# ProPrj_alba_2026-09-08.net
KiCad netlist of a schematic drawn in EasyEDA Pro
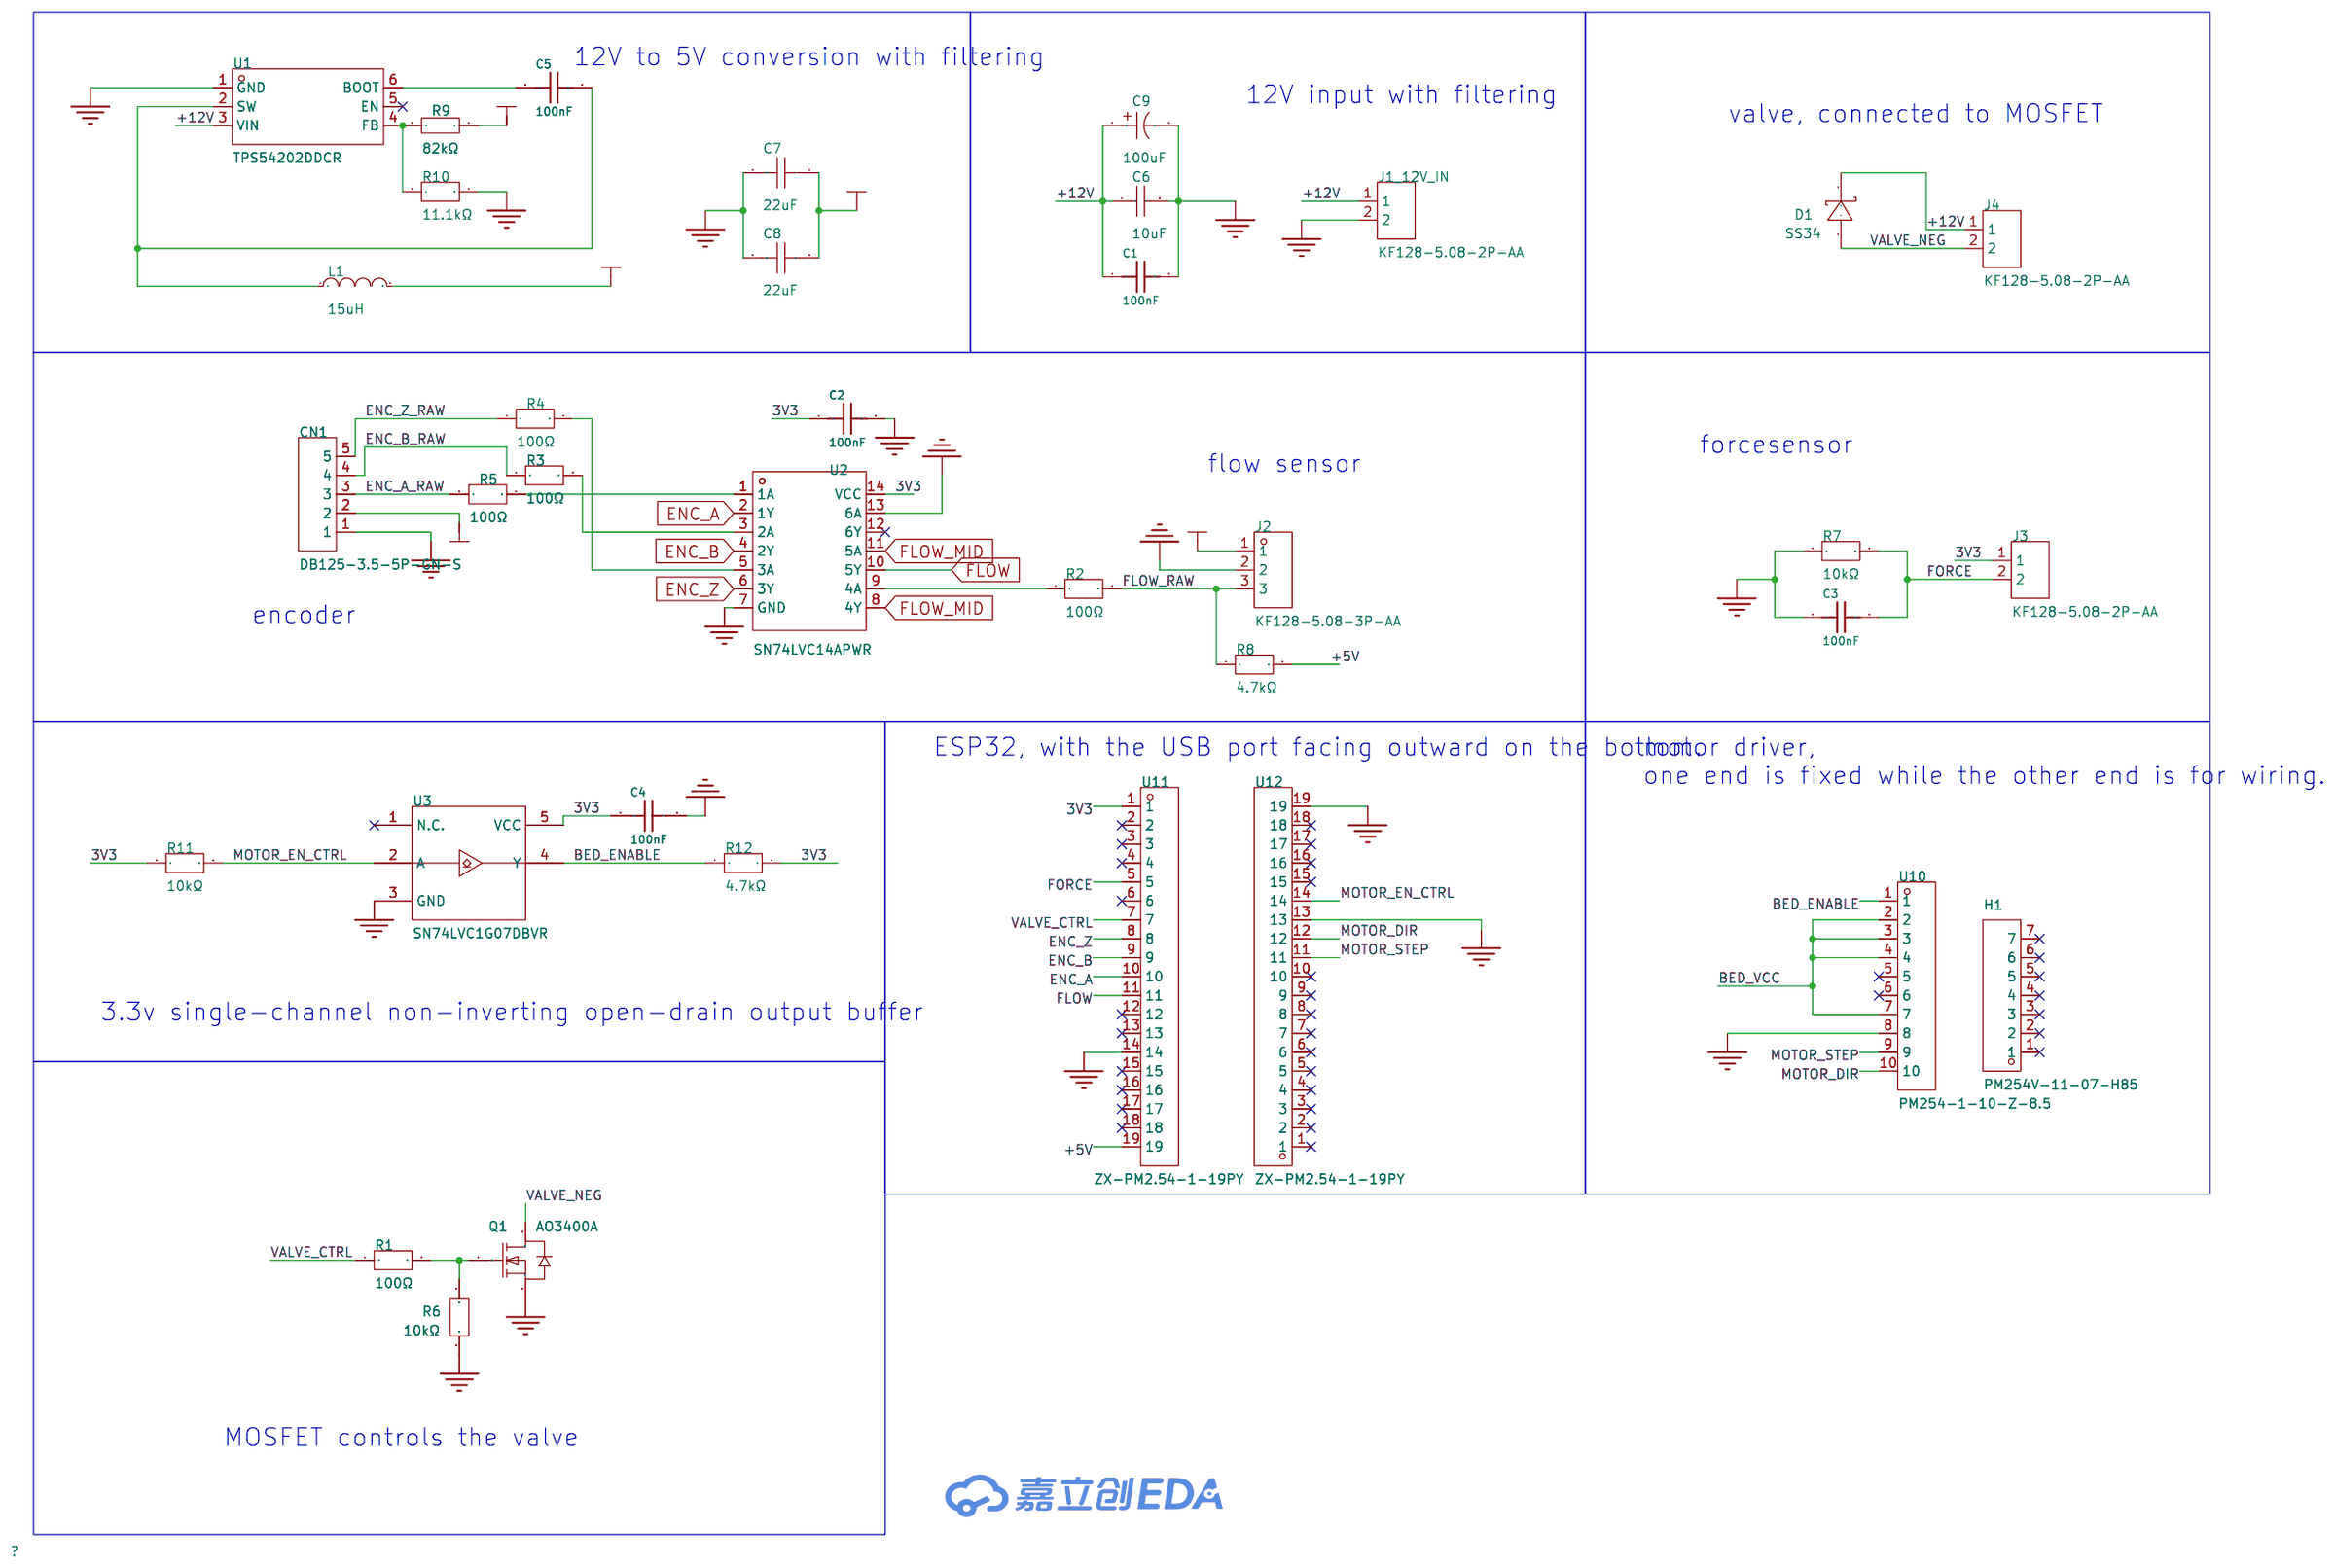
[diagram p0: schematic sheet]

(export (version "E")
  (design (tool "Eeschema 10.0.6"))
  (components
    (comp (ref "C1")
      (value "100nF")
      (footprint "easyedapro:C0603")
      (description "容值:100nF;精度:±10%;额定电压:50V;温度系数:X7R;")
      (fields
        (field (name "Manufacturer Part") "CC0603KRX7R9BB104")
        (field (name "Manufacturer") "YAGEO(国巨)")
      )
      (libsource (lib "easyedapro") (part "CC0603KRX7R9BB104"))
    )
    (comp (ref "C2")
      (value "100nF")
      (footprint "easyedapro:C0603")
      (description "容值:100nF;精度:±10%;额定电压:50V;温度系数:X7R;")
      (fields
        (field (name "Manufacturer Part") "CC0603KRX7R9BB104")
        (field (name "Manufacturer") "YAGEO(国巨)")
      )
      (libsource (lib "easyedapro") (part "CC0603KRX7R9BB104"))
    )
    (comp (ref "C3")
      (value "100nF")
      (footprint "easyedapro:C0603")
      (description "容值:100nF;精度:±10%;额定电压:50V;温度系数:X7R;")
      (fields
        (field (name "Manufacturer Part") "CC0603KRX7R9BB104")
        (field (name "Manufacturer") "YAGEO(国巨)")
      )
      (libsource (lib "easyedapro") (part "CC0603KRX7R9BB104"))
    )
    (comp (ref "C4")
      (value "100nF")
      (footprint "easyedapro:C0603")
      (description "容值:100nF;精度:±10%;额定电压:50V;温度系数:X7R;")
      (fields
        (field (name "Manufacturer Part") "CC0603KRX7R9BB104")
        (field (name "Manufacturer") "YAGEO(国巨)")
      )
      (libsource (lib "easyedapro") (part "CC0603KRX7R9BB104"))
    )
    (comp (ref "C5")
      (value "100nF")
      (footprint "easyedapro:C0603")
      (description "容值:100nF;精度:±10%;额定电压:50V;温度系数:X7R;")
      (fields
        (field (name "Manufacturer Part") "CC0603KRX7R9BB104")
        (field (name "Manufacturer") "YAGEO(国巨)")
      )
      (libsource (lib "easyedapro") (part "CC0603KRX7R9BB104"))
    )
    (comp (ref "C6")
      (value "10uF")
      (footprint "easyedapro:C1206")
      (description "容值:10uF;精度:±10%;额定电压:50V;温度系数:X5R;")
      (fields
        (field (name "Manufacturer Part") "CL31A106KBHNNNE")
        (field (name "Manufacturer") "SAMSUNG(三星)")
      )
      (libsource (lib "easyedapro") (part "CL31A106KBHNNNE"))
    )
    (comp (ref "C7")
      (value "22uF")
      (footprint "easyedapro:C1206")
      (description "容值:22uF;精度:±20%;额定电压:10V;温度系数:X5R;")
      (fields (field (name "Manufacturer Part") "1206X226M100NT") (field (name "Manufacturer") "FH(风华)"))
      (libsource (lib "easyedapro") (part "1206X226M100NT"))
    )
    (comp (ref "C8")
      (value "22uF")
      (footprint "easyedapro:C1206")
      (description "容值:22uF;精度:±20%;额定电压:10V;温度系数:X5R;")
      (fields (field (name "Manufacturer Part") "1206X226M100NT") (field (name "Manufacturer") "FH(风华)"))
      (libsource (lib "easyedapro") (part "1206X226M100NT"))
    )
    (comp (ref "C9")
      (value "100uF")
      (footprint "easyedapro:CAP-SMD_BD6.3-L6.6-W6.6-LS7.2-FD-1")
      (description "容值:100uF;精度:±20%;额定电压:25V;纹波电流:93mA@120Hz;等效串联电阻(ESR):-;")
      (fields
        (field (name "Manufacturer Part") "RVT1E101M0607 100UF 25V")
        (field (name "Manufacturer") "DMBJ(振宝佳)")
      )
      (libsource (lib "easyedapro") (part "RVT1E101M0607 100UF 25V"))
    )
    (comp (ref "CN1")
      (value "DB125-3.5-5P-GN-S")
      (footprint "easyedapro:CONN-TH_5P-P3.50_DORABO_DB125-3.5-5P-GN-S")
      (fields (field (name "Manufacturer") "DORABO(地博电气)"))
      (libsource (lib "easyedapro") (part "DB125-3.5-5P-GN-S"))
    )
    (comp (ref "D1")
      (value "SS34")
      (footprint "easyedapro:SMA_L4.3-W2.6-LS5.2-RD")
      (description "二极管配置:独立式;正向压降(Vf):550mV@3A;直流反向耐压(Vr):40V;整流电流:3A;")
      (fields (field (name "Manufacturer") "MDD(辰达半导体)"))
      (libsource (lib "easyedapro") (part "SS34_C8678"))
    )
    (comp (ref "H1")
      (value "PM254V-11-07-H85")
      (footprint "easyedapro:HDR-TH_7P-P2.54-V-F")
      (fields (field (name "Manufacturer") "XFCN(兴飞)"))
      (libsource (lib "easyedapro") (part "PM254V-11-07-H85"))
    )
    (comp (ref "J1_12V_IN")
      (value "KF128-5.08-2P-AA")
      (footprint "easyedapro:CONN-TH_P5.08_KF128-5.08-2P")
      (fields (field (name "Manufacturer") "KEFA(科发)"))
      (libsource (lib "easyedapro") (part "KF128-5.08-2P"))
    )
    (comp (ref "J2")
      (value "KF128-5.08-3P-AA")
      (footprint "easyedapro:CONN-TH_3P-P5.08_KF128-5.08-3P")
      (fields (field (name "Manufacturer") "KEFA(科发)"))
      (libsource (lib "easyedapro") (part "KF128-5.08-3P"))
    )
    (comp (ref "J3")
      (value "KF128-5.08-2P-AA")
      (footprint "easyedapro:CONN-TH_P5.08_KF128-5.08-2P")
      (fields (field (name "Manufacturer") "KEFA(科发)"))
      (libsource (lib "easyedapro") (part "KF128-5.08-2P"))
    )
    (comp (ref "J4")
      (value "KF128-5.08-2P-AA")
      (footprint "easyedapro:CONN-TH_P5.08_KF128-5.08-2P")
      (fields (field (name "Manufacturer") "KEFA(科发)"))
      (libsource (lib "easyedapro") (part "KF128-5.08-2P"))
    )
    (comp (ref "L1")
      (value "15uH")
      (footprint "easyedapro:IND-SMD_L7.2-W6.6_GPSR07X0")
      (description "电感值:15uH;精度:±20%;额定电流:3A;直流电阻(DCR):98mΩ;")
      (fields (field (name "Manufacturer Part") "CYA0630-15UH") (field (name "Manufacturer") "SHOU HAN(首韩)"))
      (libsource (lib "easyedapro") (part "CYA0630-15UH"))
    )
    (comp (ref "Q1")
      (value "AO3400A")
      (footprint "easyedapro:SOT-23-3_L2.9-W1.3-P1.90-LS2.4-BR")
      (description "数量:-;漏源电压(Vdss):30V;连续漏极电流(Id):-;导通电阻(RDS(on)):48mΩ@2.5V;耗散功率(Pd):-;阈值电压(Vgs(th)):1.45V@250uA;")
      (fields (field (name "Manufacturer") "AOS"))
      (libsource (lib "easyedapro") (part "AO3400A"))
    )
    (comp (ref "R1")
      (value "100Ω")
      (footprint "easyedapro:R0603")
      (description "电阻类型:厚膜电阻;阻值:100Ω;精度:±1%;功率:100mW;工作电压:75V;温度系数:±100ppm/°C;")
      (fields (field (name "Manufacturer Part") "FRC0603F1000TS") (field (name "Manufacturer") "FOJAN(富捷)"))
      (libsource (lib "easyedapro") (part "FRC0603F1000TS"))
    )
    (comp (ref "R2")
      (value "100Ω")
      (footprint "easyedapro:R0603")
      (description "电阻类型:厚膜电阻;阻值:100Ω;精度:±1%;功率:100mW;工作电压:75V;温度系数:±100ppm/°C;")
      (fields (field (name "Manufacturer Part") "FRC0603F1000TS") (field (name "Manufacturer") "FOJAN(富捷)"))
      (libsource (lib "easyedapro") (part "FRC0603F1000TS"))
    )
    (comp (ref "R3")
      (value "100Ω")
      (footprint "easyedapro:R0603")
      (description "电阻类型:厚膜电阻;阻值:100Ω;精度:±1%;功率:100mW;工作电压:75V;温度系数:±100ppm/°C;")
      (fields (field (name "Manufacturer Part") "FRC0603F1000TS") (field (name "Manufacturer") "FOJAN(富捷)"))
      (libsource (lib "easyedapro") (part "FRC0603F1000TS"))
    )
    (comp (ref "R4")
      (value "100Ω")
      (footprint "easyedapro:R0603")
      (description "电阻类型:厚膜电阻;阻值:100Ω;精度:±1%;功率:100mW;工作电压:75V;温度系数:±100ppm/°C;")
      (fields (field (name "Manufacturer Part") "FRC0603F1000TS") (field (name "Manufacturer") "FOJAN(富捷)"))
      (libsource (lib "easyedapro") (part "FRC0603F1000TS"))
    )
    (comp (ref "R5")
      (value "100Ω")
      (footprint "easyedapro:R0603")
      (description "电阻类型:厚膜电阻;阻值:100Ω;精度:±1%;功率:100mW;工作电压:75V;温度系数:±100ppm/°C;")
      (fields (field (name "Manufacturer Part") "FRC0603F1000TS") (field (name "Manufacturer") "FOJAN(富捷)"))
      (libsource (lib "easyedapro") (part "FRC0603F1000TS"))
    )
    (comp (ref "R6")
      (value "10kΩ")
      (footprint "easyedapro:R0603")
      (description "电阻类型:厚膜电阻;阻值:10kΩ;精度:±1%;功率:100mW;工作电压:75V;温度系数:±100ppm/°C;")
      (fields (field (name "Manufacturer Part") "FRC0603F1002TS") (field (name "Manufacturer") "FOJAN(富捷)"))
      (libsource (lib "easyedapro") (part "FRC0603F1002TS"))
    )
    (comp (ref "R7")
      (value "10kΩ")
      (footprint "easyedapro:R0603")
      (description "电阻类型:厚膜电阻;阻值:10kΩ;精度:±1%;功率:100mW;工作电压:75V;温度系数:±100ppm/°C;")
      (fields (field (name "Manufacturer Part") "FRC0603F1002TS") (field (name "Manufacturer") "FOJAN(富捷)"))
      (libsource (lib "easyedapro") (part "FRC0603F1002TS"))
    )
    (comp (ref "R8")
      (value "4.7kΩ")
      (footprint "easyedapro:R0603")
      (description "电阻类型:厚膜电阻;阻值:4.7kΩ;精度:±1%;功率:100mW;工作电压:75V;温度系数:±100ppm/°C;")
      (fields (field (name "Manufacturer Part") "FRC0603F4701TS") (field (name "Manufacturer") "FOJAN(富捷)"))
      (libsource (lib "easyedapro") (part "FRC0603F4701TS"))
    )
    (comp (ref "R9")
      (value "82kΩ")
      (footprint "easyedapro:R0603")
      (description "电阻类型:厚膜电阻;阻值:82kΩ;精度:±1%;功率:100mW;工作电压:75V;温度系数:±100ppm/°C;")
      (fields
        (field (name "Manufacturer Part") "0603WAF8202T5E")
        (field (name "Manufacturer") "UNI-ROYAL(厚声)")
      )
      (libsource (lib "easyedapro") (part "0603WAF8202T5E"))
    )
    (comp (ref "R10")
      (value "11.1kΩ")
      (footprint "easyedapro:R0603")
      (description "电阻类型:薄膜电阻;阻值:11.1kΩ;精度:±0.1%;功率:125mW;工作电压:75V;温度系数:±25ppm/°C;")
      (fields
        (field (name "Manufacturer Part") "TNPW060311K1BEEA")
        (field (name "Manufacturer") "VISHAY(威世)")
      )
      (libsource (lib "easyedapro") (part "TNPW060311K1BEEA"))
    )
    (comp (ref "R11")
      (value "10kΩ")
      (footprint "easyedapro:R0603")
      (description "电阻类型:厚膜电阻;阻值:10kΩ;精度:±1%;功率:100mW;工作电压:75V;温度系数:±100ppm/°C;")
      (fields (field (name "Manufacturer Part") "FRC0603F1002TS") (field (name "Manufacturer") "FOJAN(富捷)"))
      (libsource (lib "easyedapro") (part "FRC0603F1002TS"))
    )
    (comp (ref "R12")
      (value "4.7kΩ")
      (footprint "easyedapro:R0603")
      (description "电阻类型:厚膜电阻;阻值:4.7kΩ;精度:±1%;功率:100mW;工作电压:75V;温度系数:±100ppm/°C;")
      (fields (field (name "Manufacturer Part") "FRC0603F4701TS") (field (name "Manufacturer") "FOJAN(富捷)"))
      (libsource (lib "easyedapro") (part "FRC0603F4701TS"))
    )
    (comp (ref "U1")
      (value "TPS54202DDCR")
      (footprint "easyedapro:SOT-23-6_L2.9-W1.6-P0.95-LS2.8-BL")
      (description "功能类型:降压型;工作电压:4.5V~28V;输出电压:-;输出电流:2A;输出类型:可调;")
      (fields (field (name "Manufacturer") "TI(德州仪器)"))
      (libsource (lib "easyedapro") (part "TPS54202DDCR"))
    )
    (comp (ref "U2")
      (value "SN74LVC14APWR")
      (footprint "easyedapro:TSSOP-14_L5.0-W4.4-P0.65-LS6.4-BL")
      (description "输入类型:施密特触发器;工作电压:1.65V~3.6V;静态电流(Iq):1uA;通道数:6;传播延迟(tpd):6.2ns@3.3V,50pF;")
      (fields (field (name "Manufacturer") "TI(德州仪器)"))
      (libsource (lib "easyedapro") (part "SN74LVC14APWRG4"))
    )
    (comp (ref "U3")
      (value "SN74LVC1G07DBVR")
      (footprint "easyedapro:SOT-23-5_L3.0-W1.7-P0.95-LS2.8-BR")
      (description "输入类型:-;工作电压:1.65V~5.5V;元件数:1;每个元件位数:1;灌电流(IOL):32mA;拉电流(IOH):-;")
      (fields (field (name "Manufacturer") "TI(德州仪器)"))
      (libsource (lib "easyedapro") (part "SN74LVC1G07DBVR"))
    )
    (comp (ref "U10")
      (value "PM254-1-10-Z-8.5")
      (footprint "easyedapro:HDR-TH_10P-P2.54-V-F")
      (fields (field (name "Manufacturer") "HCTL(华灿天禄)"))
      (libsource (lib "easyedapro") (part "PM254-1-10-Z-8.5"))
    )
    (comp (ref "U11")
      (value "ZX-PM2.54-1-19PY")
      (footprint "easyedapro:HDR-TH_19P-P2.54-V-F")
      (fields (field (name "Manufacturer") "Megastar(兆星)"))
      (libsource (lib "easyedapro") (part "ZX-PM2.54-1-19PY"))
    )
    (comp (ref "U12")
      (value "ZX-PM2.54-1-19PY")
      (footprint "easyedapro:HDR-TH_19P-P2.54-V-F")
      (fields (field (name "Manufacturer") "Megastar(兆星)"))
      (libsource (lib "easyedapro") (part "ZX-PM2.54-1-19PY"))
    )
  )
  (nets
    (net (code "1") (name "+5V") (class "Default")
      (node (ref "C7") (pin "1") (pinfunction "1_1") (pintype "unspecified"))
      (node (ref "C8") (pin "1") (pinfunction "1_1") (pintype "unspecified"))
      (node (ref "CN1") (pin "2") (pinfunction "2_2") (pintype "unspecified"))
      (node (ref "J2") (pin "1") (pinfunction "1_1") (pintype "unspecified"))
      (node (ref "L1") (pin "2") (pinfunction "2_2") (pintype "unspecified"))
      (node (ref "R8") (pin "2") (pinfunction "2_2") (pintype "unspecified"))
      (node (ref "R9") (pin "2") (pinfunction "2_2") (pintype "input"))
      (node (ref "U11") (pin "19") (pinfunction "19_19") (pintype "unspecified"))
    )
    (net (code "2") (name "/+12V") (class "Default")
      (node (ref "C1") (pin "1") (pinfunction "1_1") (pintype "unspecified"))
      (node (ref "C6") (pin "1") (pinfunction "1_1") (pintype "input"))
      (node (ref "C9") (pin "1") (pinfunction "1_1") (pintype "input"))
      (node (ref "D1") (pin "1") (pinfunction "K_1") (pintype "unspecified"))
      (node (ref "J1_12V_IN") (pin "1") (pinfunction "1_1") (pintype "unspecified"))
      (node (ref "J4") (pin "1") (pinfunction "1_1") (pintype "unspecified"))
      (node (ref "U1") (pin "3") (pinfunction "VIN_3") (pintype "unspecified"))
    )
    (net (code "3") (name "/3V3") (class "Default")
      (node (ref "C2") (pin "1") (pinfunction "1_1") (pintype "unspecified"))
      (node (ref "C4") (pin "1") (pinfunction "1_1") (pintype "unspecified"))
      (node (ref "J3") (pin "1") (pinfunction "1_1") (pintype "unspecified"))
      (node (ref "R11") (pin "1") (pinfunction "1_1") (pintype "unspecified"))
      (node (ref "R12") (pin "2") (pinfunction "2_2") (pintype "unspecified"))
      (node (ref "U11") (pin "1") (pinfunction "1_1") (pintype "unspecified"))
      (node (ref "U2") (pin "14") (pinfunction "VCC_14") (pintype "unspecified"))
      (node (ref "U3") (pin "5") (pinfunction "VCC_5") (pintype "unspecified"))
    )
    (net (code "4") (name "/BED_ENABLE") (class "Default")
      (node (ref "R12") (pin "1") (pinfunction "1_1") (pintype "unspecified"))
      (node (ref "U10") (pin "1") (pinfunction "1_1") (pintype "unspecified"))
      (node (ref "U3") (pin "4") (pinfunction "Y_4") (pintype "unspecified"))
    )
    (net (code "5") (name "/BED_VCC") (class "Default")
      (node (ref "U10") (pin "2") (pinfunction "2_2") (pintype "unspecified"))
      (node (ref "U10") (pin "3") (pinfunction "3_3") (pintype "unspecified"))
      (node (ref "U10") (pin "4") (pinfunction "4_4") (pintype "unspecified"))
      (node (ref "U10") (pin "7") (pinfunction "7_7") (pintype "unspecified"))
    )
    (net (code "6") (name "/ENC_A_RAW") (class "Default")
      (node (ref "CN1") (pin "3") (pinfunction "3_3") (pintype "unspecified"))
      (node (ref "R5") (pin "1") (pinfunction "1_1") (pintype "unspecified"))
    )
    (net (code "7") (name "/ENC_B_RAW") (class "Default")
      (node (ref "CN1") (pin "4") (pinfunction "4_4") (pintype "unspecified"))
      (node (ref "R3") (pin "1") (pinfunction "1_1") (pintype "unspecified"))
    )
    (net (code "8") (name "/ENC_Z_RAW") (class "Default")
      (node (ref "CN1") (pin "5") (pinfunction "5_5") (pintype "unspecified"))
      (node (ref "R4") (pin "1") (pinfunction "1_1") (pintype "unspecified"))
    )
    (net (code "9") (name "/FLOW_RAW") (class "Default")
      (node (ref "J2") (pin "3") (pinfunction "3_3") (pintype "unspecified"))
      (node (ref "R2") (pin "2") (pinfunction "2_2") (pintype "unspecified"))
      (node (ref "R8") (pin "1") (pinfunction "1_1") (pintype "unspecified"))
    )
    (net (code "10") (name "/FORCE") (class "Default")
      (node (ref "C3") (pin "2") (pinfunction "2_2") (pintype "unspecified"))
      (node (ref "J3") (pin "2") (pinfunction "2_2") (pintype "unspecified"))
      (node (ref "R7") (pin "2") (pinfunction "2_2") (pintype "unspecified"))
      (node (ref "U11") (pin "5") (pinfunction "5_5") (pintype "unspecified"))
    )
    (net (code "11") (name "/MOTOR_DIR") (class "Default")
      (node (ref "U10") (pin "10") (pinfunction "10_10") (pintype "unspecified"))
      (node (ref "U12") (pin "12") (pinfunction "12_12") (pintype "unspecified"))
    )
    (net (code "12") (name "/MOTOR_EN_CTRL") (class "Default")
      (node (ref "R11") (pin "2") (pinfunction "2_2") (pintype "unspecified"))
      (node (ref "U12") (pin "14") (pinfunction "14_14") (pintype "unspecified"))
      (node (ref "U3") (pin "2") (pinfunction "A_2") (pintype "unspecified"))
    )
    (net (code "13") (name "/MOTOR_STEP") (class "Default")
      (node (ref "U10") (pin "9") (pinfunction "9_9") (pintype "unspecified"))
      (node (ref "U12") (pin "11") (pinfunction "11_11") (pintype "unspecified"))
    )
    (net (code "14") (name "/VALVE_CTRL") (class "Default")
      (node (ref "R1") (pin "1") (pinfunction "1_1") (pintype "unspecified"))
      (node (ref "U11") (pin "7") (pinfunction "7_7") (pintype "unspecified"))
    )
    (net (code "15") (name "/VALVE_NEG") (class "Default")
      (node (ref "D1") (pin "2") (pinfunction "A_2") (pintype "unspecified"))
      (node (ref "J4") (pin "2") (pinfunction "2_2") (pintype "unspecified"))
      (node (ref "Q1") (pin "3") (pinfunction "D_3") (pintype "unspecified"))
    )
    (net (code "16") (name "ENC_A") (class "Default")
      (node (ref "U11") (pin "10") (pinfunction "10_10") (pintype "unspecified"))
      (node (ref "U2") (pin "2") (pinfunction "1Y_2") (pintype "unspecified"))
    )
    (net (code "17") (name "ENC_B") (class "Default")
      (node (ref "U11") (pin "9") (pinfunction "9_9") (pintype "unspecified"))
      (node (ref "U2") (pin "4") (pinfunction "2Y_4") (pintype "unspecified"))
    )
    (net (code "18") (name "ENC_Z") (class "Default")
      (node (ref "U11") (pin "8") (pinfunction "8_8") (pintype "unspecified"))
      (node (ref "U2") (pin "6") (pinfunction "3Y_6") (pintype "unspecified"))
    )
    (net (code "19") (name "FLOW") (class "Default")
      (node (ref "U11") (pin "11") (pinfunction "11_11") (pintype "unspecified"))
      (node (ref "U2") (pin "10") (pinfunction "5Y_10") (pintype "unspecified"))
    )
    (net (code "20") (name "FLOW_MID") (class "Default")
      (node (ref "U2") (pin "11") (pinfunction "5A_11") (pintype "unspecified"))
      (node (ref "U2") (pin "8") (pinfunction "4Y_8") (pintype "unspecified"))
    )
    (net (code "21") (name "GND") (class "Default")
      (node (ref "C1") (pin "2") (pinfunction "2_2") (pintype "unspecified"))
      (node (ref "C2") (pin "2") (pinfunction "2_2") (pintype "unspecified"))
      (node (ref "C3") (pin "1") (pinfunction "1_1") (pintype "unspecified"))
      (node (ref "C4") (pin "2") (pinfunction "2_2") (pintype "unspecified"))
      (node (ref "C6") (pin "2") (pinfunction "2_2") (pintype "input"))
      (node (ref "C7") (pin "2") (pinfunction "2_2") (pintype "unspecified"))
      (node (ref "C8") (pin "2") (pinfunction "2_2") (pintype "unspecified"))
      (node (ref "C9") (pin "2") (pinfunction "2_2") (pintype "input"))
      (node (ref "CN1") (pin "1") (pinfunction "1_1") (pintype "unspecified"))
      (node (ref "J1_12V_IN") (pin "2") (pinfunction "2_2") (pintype "unspecified"))
      (node (ref "J2") (pin "2") (pinfunction "2_2") (pintype "unspecified"))
      (node (ref "Q1") (pin "2") (pinfunction "S_2") (pintype "unspecified"))
      (node (ref "R10") (pin "2") (pinfunction "2_2") (pintype "unspecified"))
      (node (ref "R6") (pin "1") (pinfunction "1_1") (pintype "unspecified"))
      (node (ref "R7") (pin "1") (pinfunction "1_1") (pintype "unspecified"))
      (node (ref "U1") (pin "1") (pinfunction "GND_1") (pintype "unspecified"))
      (node (ref "U10") (pin "8") (pinfunction "8_8") (pintype "unspecified"))
      (node (ref "U11") (pin "14") (pinfunction "14_14") (pintype "unspecified"))
      (node (ref "U12") (pin "13") (pinfunction "13_13") (pintype "unspecified"))
      (node (ref "U12") (pin "19") (pinfunction "19_19") (pintype "unspecified"))
      (node (ref "U2") (pin "13") (pinfunction "6A_13") (pintype "unspecified"))
      (node (ref "U2") (pin "7") (pinfunction "GND_7") (pintype "unspecified"))
      (node (ref "U3") (pin "3") (pinfunction "GND_3") (pintype "unspecified"))
    )
    (net (code "22") (name "Net-(Q1-G)") (class "Default")
      (node (ref "Q1") (pin "1") (pinfunction "G_1") (pintype "unspecified"))
      (node (ref "R1") (pin "2") (pinfunction "2_2") (pintype "unspecified"))
      (node (ref "R6") (pin "2") (pinfunction "2_2") (pintype "unspecified"))
    )
    (net (code "23") (name "Net-(U1-BOOT)") (class "Default")
      (node (ref "C5") (pin "1") (pinfunction "1_1") (pintype "unspecified"))
      (node (ref "U1") (pin "6") (pinfunction "BOOT_6") (pintype "unspecified"))
    )
    (net (code "24") (name "Net-(U1-FB)") (class "Default")
      (node (ref "R10") (pin "1") (pinfunction "1_1") (pintype "unspecified"))
      (node (ref "R9") (pin "1") (pinfunction "1_1") (pintype "input"))
      (node (ref "U1") (pin "4") (pinfunction "FB_4") (pintype "unspecified"))
    )
    (net (code "25") (name "Net-(U1-SW)") (class "Default")
      (node (ref "C5") (pin "2") (pinfunction "2_2") (pintype "unspecified"))
      (node (ref "L1") (pin "1") (pinfunction "1_1") (pintype "unspecified"))
      (node (ref "U1") (pin "2") (pinfunction "SW_2") (pintype "unspecified"))
    )
    (net (code "26") (name "Net-(U2-1A)") (class "Default")
      (node (ref "R5") (pin "2") (pinfunction "2_2") (pintype "unspecified"))
      (node (ref "U2") (pin "1") (pinfunction "1A_1") (pintype "unspecified"))
    )
    (net (code "27") (name "Net-(U2-2A)") (class "Default")
      (node (ref "R3") (pin "2") (pinfunction "2_2") (pintype "unspecified"))
      (node (ref "U2") (pin "3") (pinfunction "2A_3") (pintype "unspecified"))
    )
    (net (code "28") (name "Net-(U2-3A)") (class "Default")
      (node (ref "R4") (pin "2") (pinfunction "2_2") (pintype "unspecified"))
      (node (ref "U2") (pin "5") (pinfunction "3A_5") (pintype "unspecified"))
    )
    (net (code "29") (name "Net-(U2-4A)") (class "Default")
      (node (ref "R2") (pin "1") (pinfunction "1_1") (pintype "unspecified"))
      (node (ref "U2") (pin "9") (pinfunction "4A_9") (pintype "unspecified"))
    )
    (net (code "30") (name "unconnected-(H1-Pad1)") (class "Default")
      (node (ref "H1") (pin "1") (pinfunction "1_1") (pintype "unspecified+no_connect"))
    )
    (net (code "31") (name "unconnected-(H1-Pad2)") (class "Default")
      (node (ref "H1") (pin "2") (pinfunction "2_2") (pintype "unspecified+no_connect"))
    )
    (net (code "32") (name "unconnected-(H1-Pad3)") (class "Default")
      (node (ref "H1") (pin "3") (pinfunction "3_3") (pintype "unspecified+no_connect"))
    )
    (net (code "33") (name "unconnected-(H1-Pad4)") (class "Default")
      (node (ref "H1") (pin "4") (pinfunction "4_4") (pintype "unspecified+no_connect"))
    )
    (net (code "34") (name "unconnected-(H1-Pad5)") (class "Default")
      (node (ref "H1") (pin "5") (pinfunction "5_5") (pintype "unspecified+no_connect"))
    )
    (net (code "35") (name "unconnected-(H1-Pad6)") (class "Default")
      (node (ref "H1") (pin "6") (pinfunction "6_6") (pintype "unspecified+no_connect"))
    )
    (net (code "36") (name "unconnected-(H1-Pad7)") (class "Default")
      (node (ref "H1") (pin "7") (pinfunction "7_7") (pintype "unspecified+no_connect"))
    )
    (net (code "37") (name "unconnected-(U1-EN-Pad5)") (class "Default")
      (node (ref "U1") (pin "5") (pinfunction "EN_5") (pintype "unspecified+no_connect"))
    )
    (net (code "38") (name "unconnected-(U2-6Y-Pad12)") (class "Default")
      (node (ref "U2") (pin "12") (pinfunction "6Y_12") (pintype "unspecified+no_connect"))
    )
    (net (code "39") (name "unconnected-(U3-N.C.-Pad1)") (class "Default")
      (node (ref "U3") (pin "1") (pinfunction "N.C._1") (pintype "unspecified+no_connect"))
    )
    (net (code "40") (name "unconnected-(U10-Pad5)") (class "Default")
      (node (ref "U10") (pin "5") (pinfunction "5_5") (pintype "unspecified+no_connect"))
    )
    (net (code "41") (name "unconnected-(U10-Pad6)") (class "Default")
      (node (ref "U10") (pin "6") (pinfunction "6_6") (pintype "unspecified+no_connect"))
    )
    (net (code "42") (name "unconnected-(U11-Pad2)") (class "Default")
      (node (ref "U11") (pin "2") (pinfunction "2_2") (pintype "unspecified+no_connect"))
    )
    (net (code "43") (name "unconnected-(U11-Pad3)") (class "Default")
      (node (ref "U11") (pin "3") (pinfunction "3_3") (pintype "unspecified+no_connect"))
    )
    (net (code "44") (name "unconnected-(U11-Pad4)") (class "Default")
      (node (ref "U11") (pin "4") (pinfunction "4_4") (pintype "unspecified+no_connect"))
    )
    (net (code "45") (name "unconnected-(U11-Pad6)") (class "Default")
      (node (ref "U11") (pin "6") (pinfunction "6_6") (pintype "unspecified+no_connect"))
    )
    (net (code "46") (name "unconnected-(U11-Pad12)") (class "Default")
      (node (ref "U11") (pin "12") (pinfunction "12_12") (pintype "unspecified+no_connect"))
    )
    (net (code "47") (name "unconnected-(U11-Pad13)") (class "Default")
      (node (ref "U11") (pin "13") (pinfunction "13_13") (pintype "unspecified+no_connect"))
    )
    (net (code "48") (name "unconnected-(U11-Pad15)") (class "Default")
      (node (ref "U11") (pin "15") (pinfunction "15_15") (pintype "unspecified+no_connect"))
    )
    (net (code "49") (name "unconnected-(U11-Pad16)") (class "Default")
      (node (ref "U11") (pin "16") (pinfunction "16_16") (pintype "unspecified+no_connect"))
    )
    (net (code "50") (name "unconnected-(U11-Pad17)") (class "Default")
      (node (ref "U11") (pin "17") (pinfunction "17_17") (pintype "unspecified+no_connect"))
    )
    (net (code "51") (name "unconnected-(U11-Pad18)") (class "Default")
      (node (ref "U11") (pin "18") (pinfunction "18_18") (pintype "unspecified+no_connect"))
    )
    (net (code "52") (name "unconnected-(U12-Pad1)") (class "Default")
      (node (ref "U12") (pin "1") (pinfunction "1_1") (pintype "unspecified+no_connect"))
    )
    (net (code "53") (name "unconnected-(U12-Pad2)") (class "Default")
      (node (ref "U12") (pin "2") (pinfunction "2_2") (pintype "unspecified+no_connect"))
    )
    (net (code "54") (name "unconnected-(U12-Pad3)") (class "Default")
      (node (ref "U12") (pin "3") (pinfunction "3_3") (pintype "unspecified+no_connect"))
    )
    (net (code "55") (name "unconnected-(U12-Pad4)") (class "Default")
      (node (ref "U12") (pin "4") (pinfunction "4_4") (pintype "unspecified+no_connect"))
    )
    (net (code "56") (name "unconnected-(U12-Pad5)") (class "Default")
      (node (ref "U12") (pin "5") (pinfunction "5_5") (pintype "unspecified+no_connect"))
    )
    (net (code "57") (name "unconnected-(U12-Pad6)") (class "Default")
      (node (ref "U12") (pin "6") (pinfunction "6_6") (pintype "unspecified+no_connect"))
    )
    (net (code "58") (name "unconnected-(U12-Pad7)") (class "Default")
      (node (ref "U12") (pin "7") (pinfunction "7_7") (pintype "unspecified+no_connect"))
    )
    (net (code "59") (name "unconnected-(U12-Pad8)") (class "Default")
      (node (ref "U12") (pin "8") (pinfunction "8_8") (pintype "unspecified+no_connect"))
    )
    (net (code "60") (name "unconnected-(U12-Pad9)") (class "Default")
      (node (ref "U12") (pin "9") (pinfunction "9_9") (pintype "unspecified+no_connect"))
    )
    (net (code "61") (name "unconnected-(U12-Pad10)") (class "Default")
      (node (ref "U12") (pin "10") (pinfunction "10_10") (pintype "unspecified+no_connect"))
    )
    (net (code "62") (name "unconnected-(U12-Pad15)") (class "Default")
      (node (ref "U12") (pin "15") (pinfunction "15_15") (pintype "unspecified+no_connect"))
    )
    (net (code "63") (name "unconnected-(U12-Pad16)") (class "Default")
      (node (ref "U12") (pin "16") (pinfunction "16_16") (pintype "unspecified+no_connect"))
    )
    (net (code "64") (name "unconnected-(U12-Pad17)") (class "Default")
      (node (ref "U12") (pin "17") (pinfunction "17_17") (pintype "unspecified+no_connect"))
    )
    (net (code "65") (name "unconnected-(U12-Pad18)") (class "Default")
      (node (ref "U12") (pin "18") (pinfunction "18_18") (pintype "unspecified+no_connect"))
    )
  )
)
